# EPS_Distribution_LCL-FPF.net
KiCad netlist of a schematic drawn in Altium Designer
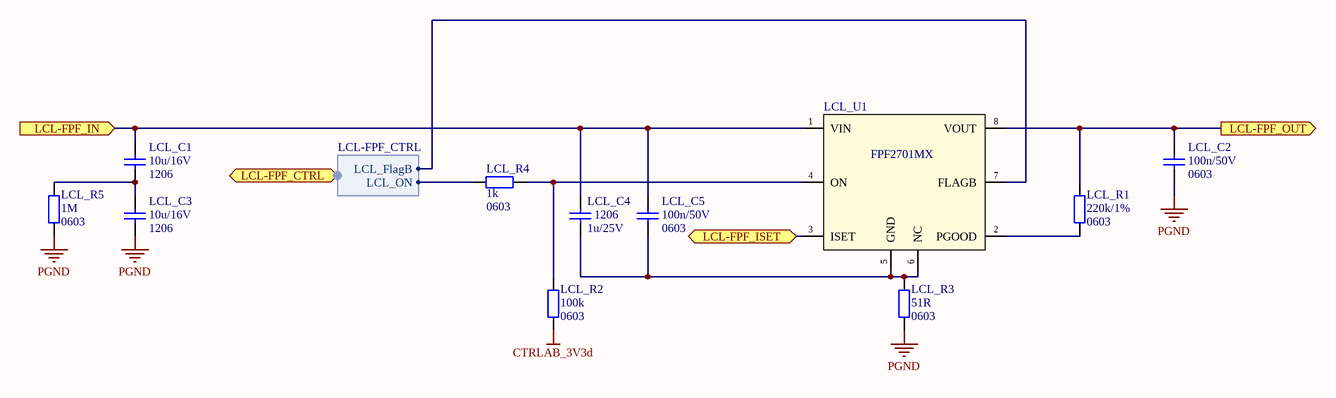
[diagram p0: EPS_Distribution_LCL-FPF.SchDoc]

(export (version "E")
  (design (tool "Eeschema 10.0.6"))
  (components
    (comp (ref "LCL_C1")
      (value "10u/16V")
      (footprint "SMD_Capacitor_1206")
      (description "Ceramic Cap Kemet COTS 10u/16V X7R 1206")
      (fields
        (field (name "MANUFACTURERPARTNUMBER") "C1206T106K4RACTU")
        (field (name "MANUFACTURER") "Kemet")
        (field (name "PACKGE") "1206")
      )
      (libsource (lib "capacitors") (part "Cer_C1206T106K4RACTU"))
    )
    (comp (ref "LCL_C2")
      (value "100n/50V")
      (footprint "SMD_Capacitor_0603")
      (description "Ceramic Cap Kemet COTS 100n/50V X7R 0603")
      (fields
        (field (name "MANUFACTURER") "Kemet")
        (field (name "MANUFACTURERPARTNUMBER") "C0603T104K5RALTU")
        (field (name "PACKAGE") "0603")
      )
      (libsource (lib "capacitors") (part "Cer_C0603T104K5RALTU"))
    )
    (comp (ref "LCL_C3")
      (value "10u/16V")
      (footprint "SMD_Capacitor_1206")
      (description "Ceramic Cap Kemet COTS 10u/16V X7R 1206")
      (fields
        (field (name "MANUFACTURERPARTNUMBER") "C1206T106K4RACTU")
        (field (name "MANUFACTURER") "Kemet")
        (field (name "PACKGE") "1206")
      )
      (libsource (lib "capacitors") (part "Cer_C1206T106K4RACTU"))
    )
    (comp (ref "LCL_C4")
      (value "1u/25V")
      (footprint "SMD_Capacitor_1206")
      (description "Ceramic Cap Kemet COTS 1u/25V X7R 1206")
      (fields
        (field (name "MANUFACTURERPARTNUMBER") "C1206T105K3RALTU")
        (field (name "MANUFACTURER") "Kemet")
        (field (name "PACKAGE") "1206")
      )
      (libsource (lib "capacitors") (part "Cer_C1206T105K3RALTU"))
    )
    (comp (ref "LCL_C5")
      (value "100n/50V")
      (footprint "SMD_Capacitor_0603")
      (description "Ceramic Cap Kemet COTS 100n/50V X7R 0603")
      (fields
        (field (name "MANUFACTURER") "Kemet")
        (field (name "MANUFACTURERPARTNUMBER") "C0603T104K5RALTU")
        (field (name "PACKAGE") "0603")
      )
      (libsource (lib "capacitors") (part "Cer_C0603T104K5RALTU"))
    )
    (comp (ref "LCL_R1")
      (value "220k/1%")
      (footprint "SMD_Resistor_0603")
      (fields (field (name "PACKAGE") "0603"))
      (libsource (lib "resistors") (part "Res"))
    )
    (comp (ref "LCL_R2")
      (value "100k")
      (footprint "SMD_Resistor_0603")
      (fields (field (name "PACKAGE") "0603"))
      (libsource (lib "resistors") (part "Res"))
    )
    (comp (ref "LCL_R3")
      (value "51R")
      (footprint "SMD_Resistor_0603")
      (fields (field (name "PACKAGE") "0603"))
      (libsource (lib "resistors") (part "Res"))
    )
    (comp (ref "LCL_R4")
      (value "1k")
      (footprint "SMD_Resistor_0603")
      (fields (field (name "PACKAGE") "0603"))
      (libsource (lib "") (part "Res_1"))
    )
    (comp (ref "LCL_R5")
      (value "1M")
      (footprint "SMD_Resistor_0603")
      (fields (field (name "PACKAGE") "0603"))
      (libsource (lib "resistors") (part "Res"))
    )
    (comp (ref "LCL_U1")
      (value "FPF2701MX")
      (footprint "SOIC-8-N")
      (description "Adj over-current protection 0.4-2A, Load Switch")
      (fields (field (name "MANUFACTURER") "Fairchild Semiconductor"))
      (libsource (lib "microcircuits") (part "FPF2701MX"))
    )
  )
  (nets
    (net (code "2") (name "/LCL-FPF_IN") (class "Default")
      (node (ref "LCL_C1") (pin "1") (pinfunction "1_1") (pintype "passive"))
      (node (ref "LCL_C4") (pin "1") (pinfunction "1_1") (pintype "passive"))
      (node (ref "LCL_C5") (pin "1") (pinfunction "1_1") (pintype "passive"))
      (node (ref "LCL_U1") (pin "1") (pinfunction "VIN_1") (pintype "passive"))
    )
    (net (code "3") (name "/LCL-FPF_ISET") (class "Default")
      (node (ref "LCL_U1") (pin "3") (pinfunction "ISET_3") (pintype "passive"))
    )
    (net (code "4") (name "/LCL-FPF_OUT") (class "Default")
      (node (ref "LCL_C2") (pin "1") (pinfunction "1_1") (pintype "passive"))
      (node (ref "LCL_R1") (pin "2") (pinfunction "2_2") (pintype "passive"))
      (node (ref "LCL_U1") (pin "8") (pinfunction "VOUT_8") (pintype "passive"))
    )
    (net (code "5") (name "/LCL_FlagB") (class "Default")
      (node (ref "LCL_U1") (pin "7") (pinfunction "FLAGB_7") (pintype "passive"))
    )
    (net (code "6") (name "/LCL_ON") (class "Default")
      (node (ref "LCL_R4") (pin "2") (pinfunction "2_2") (pintype "passive"))
    )
    (net (code "8") (name "CTRLAB_3V3d") (class "Default")
      (node (ref "LCL_R2") (pin "1") (pinfunction "1_1") (pintype "passive"))
    )
    (net (code "9") (name "Net-(LCL_C1-Pad2)") (class "Default")
      (node (ref "LCL_C1") (pin "2") (pinfunction "2_2") (pintype "passive"))
      (node (ref "LCL_C3") (pin "1") (pinfunction "1_1") (pintype "passive"))
      (node (ref "LCL_R5") (pin "2") (pinfunction "2_2") (pintype "passive"))
    )
    (net (code "10") (name "Net-(LCL_U1-GND)") (class "Default")
      (node (ref "LCL_C4") (pin "2") (pinfunction "2_2") (pintype "passive"))
      (node (ref "LCL_C5") (pin "2") (pinfunction "2_2") (pintype "passive"))
      (node (ref "LCL_R3") (pin "2") (pinfunction "2_2") (pintype "passive"))
      (node (ref "LCL_U1") (pin "5") (pinfunction "GND_5") (pintype "passive"))
      (node (ref "LCL_U1") (pin "6") (pinfunction "NC_6") (pintype "passive"))
    )
    (net (code "11") (name "Net-(LCL_U1-ON)") (class "Default")
      (node (ref "LCL_R2") (pin "2") (pinfunction "2_2") (pintype "passive"))
      (node (ref "LCL_R4") (pin "1") (pinfunction "1_1") (pintype "passive"))
      (node (ref "LCL_U1") (pin "4") (pinfunction "ON_4") (pintype "passive"))
    )
    (net (code "12") (name "Net-(LCL_U1-PGOOD)") (class "Default")
      (node (ref "LCL_R1") (pin "1") (pinfunction "1_1") (pintype "passive"))
      (node (ref "LCL_U1") (pin "2") (pinfunction "PGOOD_2") (pintype "passive"))
    )
    (net (code "13") (name "PGND") (class "Default")
      (node (ref "LCL_C2") (pin "2") (pinfunction "2_2") (pintype "passive"))
      (node (ref "LCL_C3") (pin "2") (pinfunction "2_2") (pintype "passive"))
      (node (ref "LCL_R3") (pin "1") (pinfunction "1_1") (pintype "passive"))
      (node (ref "LCL_R5") (pin "1") (pinfunction "1_1") (pintype "passive"))
    )
  )
)
